# Balloon.net
KiCad netlist of a schematic drawn in EAGLE
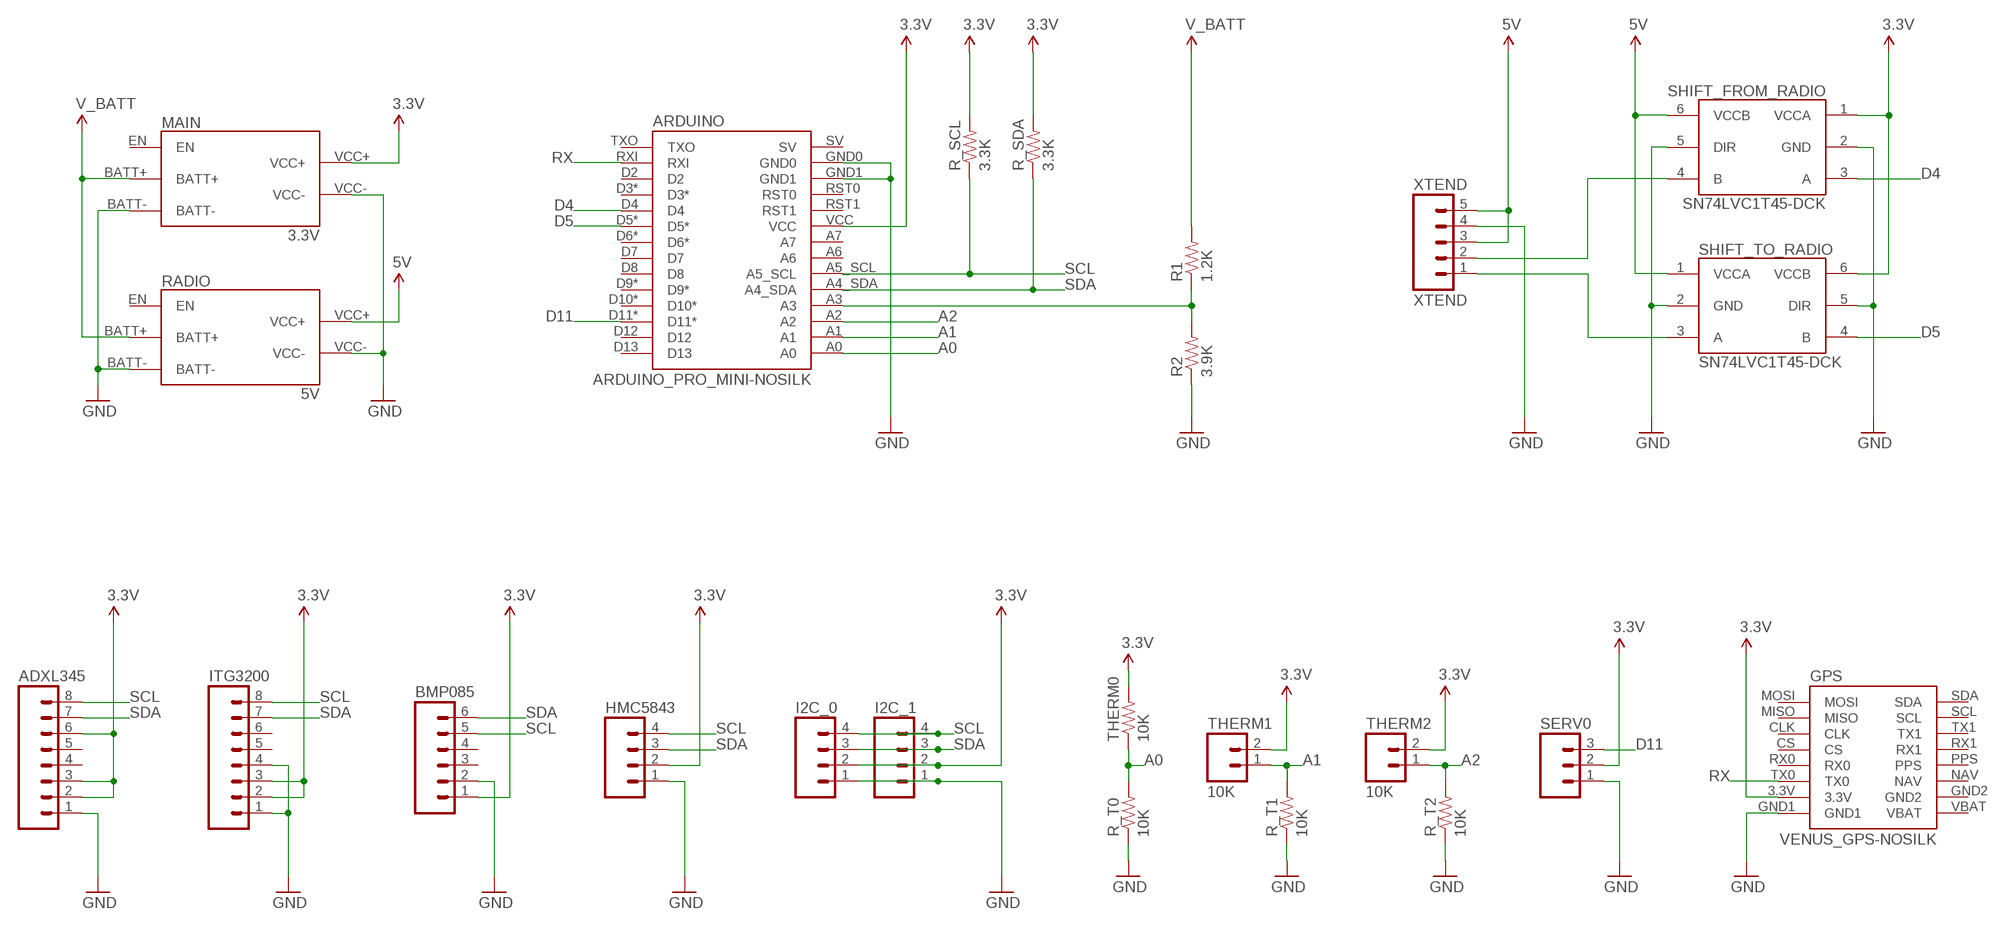
[diagram p0: schematic, sheet 1]

(export (version "E")
  (design (tool "Eeschema 10.0.6"))
  (components
    (comp (ref "ADXL345")
      (value "M081X08")
      (footprint "eagle-import:1X08")
      (libsource (lib "eagle-import") (part "M081X08"))
    )
    (comp (ref "ARDUINO")
      (value "ARDUINO_PRO_MINI-NOSILK")
      (footprint "eagle-import:ARDUINO_PRO_MINI-NOSILK")
      (libsource (lib "eagle-import") (part "ARDUINO_PRO_MINI-NOSILK"))
    )
    (comp (ref "BMP085")
      (value "M06SIP")
      (footprint "eagle-import:1X06")
      (libsource (lib "eagle-import") (part "M06SIP"))
    )
    (comp (ref "GPS")
      (value "VENUS_GPS-NOSILK")
      (footprint "eagle-import:VENUS_GPS-NOSILK")
      (libsource (lib "eagle-import") (part "VENUS_GPS-NOSILK"))
    )
    (comp (ref "HMC5843")
      (value "M04PTH")
      (footprint "eagle-import:1X04")
      (libsource (lib "eagle-import") (part "M04PTH"))
    )
    (comp (ref "I2C_0")
      (value "M04PTH")
      (footprint "eagle-import:1X04")
      (libsource (lib "eagle-import") (part "SparkFun-Connectors_M04PTH"))
    )
    (comp (ref "I2C_1")
      (value "M04PTH")
      (footprint "eagle-import:1X04")
      (libsource (lib "eagle-import") (part "SparkFun-Connectors_M04PTH"))
    )
    (comp (ref "ITG3200")
      (value "M081X08")
      (footprint "eagle-import:1X08")
      (libsource (lib "eagle-import") (part "M081X08"))
    )
    (comp (ref "MAIN")
      (value "3.3V")
      (footprint "eagle-import:POWER-TPS6300X-NOSILK")
      (libsource (lib "eagle-import") (part "POWER-TPS6300X-NOSILK"))
    )
    (comp (ref "R1")
      (value "1.2K")
      (footprint "eagle-import:0805")
      (libsource (lib "eagle-import") (part "RESISTOR0805-RES"))
    )
    (comp (ref "R2")
      (value "3.9K")
      (footprint "eagle-import:0805")
      (libsource (lib "eagle-import") (part "RESISTOR0805-RES"))
    )
    (comp (ref "RADIO")
      (value "5V")
      (footprint "eagle-import:POWER-TPS6300X-NOSILK")
      (libsource (lib "eagle-import") (part "POWER-TPS6300X-NOSILK"))
    )
    (comp (ref "R_SCL")
      (value "3.3K")
      (footprint "eagle-import:0805")
      (libsource (lib "eagle-import") (part "RESISTOR0805-RES"))
    )
    (comp (ref "R_SDA")
      (value "3.3K")
      (footprint "eagle-import:0805")
      (libsource (lib "eagle-import") (part "RESISTOR0805-RES"))
    )
    (comp (ref "R_T0")
      (value "10K")
      (footprint "eagle-import:0805")
      (libsource (lib "eagle-import") (part "RESISTOR0805-RES"))
    )
    (comp (ref "R_T1")
      (value "10K")
      (footprint "eagle-import:0805")
      (libsource (lib "eagle-import") (part "RESISTOR0805-RES"))
    )
    (comp (ref "R_T2")
      (value "10K")
      (footprint "eagle-import:0805")
      (libsource (lib "eagle-import") (part "RESISTOR0805-RES"))
    )
    (comp (ref "SERV0")
      (value "M03PTH")
      (footprint "eagle-import:1X03")
      (libsource (lib "eagle-import") (part "M03PTH"))
    )
    (comp (ref "SHIFT_FROM_RADIO")
      (value "SN74LVC1T45-DCK")
      (footprint "eagle-import:SC70")
      (libsource (lib "eagle-import") (part "SN74LVC1T45-DCK"))
    )
    (comp (ref "SHIFT_TO_RADIO")
      (value "SN74LVC1T45-DCK")
      (footprint "eagle-import:SC70")
      (libsource (lib "eagle-import") (part "SN74LVC1T45-DCK"))
    )
    (comp (ref "THERM0")
      (value "10K")
      (footprint "eagle-import:0805")
      (libsource (lib "eagle-import") (part "RESISTOR0805-RES"))
    )
    (comp (ref "THERM1")
      (value "10K")
      (footprint "eagle-import:JST-2-PTH")
      (libsource (lib "eagle-import") (part "M02JST-PTH-2"))
    )
    (comp (ref "THERM2")
      (value "10K")
      (footprint "eagle-import:JST-2-PTH")
      (libsource (lib "eagle-import") (part "M02JST-PTH-2"))
    )
    (comp (ref "XTEND")
      (value "XTEND")
      (footprint "eagle-import:JST-5-PTH-VERT")
      (libsource (lib "eagle-import") (part "M05JST-PTH-VERT"))
    )
  )
  (nets
    (net (code "1") (name "/A0") (class "Default")
      (node (ref "ARDUINO") (pin "A0") (pinfunction "A0_A0") (pintype "bidirectional"))
      (node (ref "R_T0") (pin "2") (pinfunction "2_2") (pintype "passive"))
      (node (ref "THERM0") (pin "1") (pinfunction "1_1") (pintype "passive"))
    )
    (net (code "2") (name "/A1") (class "Default")
      (node (ref "ARDUINO") (pin "A1") (pinfunction "A1_A1") (pintype "bidirectional"))
      (node (ref "R_T1") (pin "2") (pinfunction "2_2") (pintype "passive"))
      (node (ref "THERM1") (pin "1") (pinfunction "1_1") (pintype "passive"))
    )
    (net (code "3") (name "/A2") (class "Default")
      (node (ref "ARDUINO") (pin "A2") (pinfunction "A2_A2") (pintype "bidirectional"))
      (node (ref "R_T2") (pin "2") (pinfunction "2_2") (pintype "passive"))
      (node (ref "THERM2") (pin "1") (pinfunction "1_1") (pintype "passive"))
    )
    (net (code "4") (name "/D4") (class "Default")
      (node (ref "ARDUINO") (pin "D4") (pinfunction "D4_D4") (pintype "bidirectional"))
      (node (ref "SHIFT_FROM_RADIO") (pin "3") (pinfunction "A_3") (pintype "bidirectional"))
    )
    (net (code "5") (name "/D5") (class "Default")
      (node (ref "ARDUINO") (pin "D5*") (pinfunction "D5*_D5*") (pintype "bidirectional"))
      (node (ref "SHIFT_TO_RADIO") (pin "4") (pinfunction "B_4") (pintype "bidirectional"))
    )
    (net (code "6") (name "/D11") (class "Default")
      (node (ref "ARDUINO") (pin "D11*") (pinfunction "D11*_D11*") (pintype "bidirectional"))
      (node (ref "SERV0") (pin "3") (pinfunction "3_3") (pintype "passive"))
    )
    (net (code "7") (name "/RX") (class "Default")
      (node (ref "ARDUINO") (pin "RXI") (pinfunction "RXI_RXI") (pintype "bidirectional"))
      (node (ref "GPS") (pin "TX0") (pinfunction "TX0_TX0") (pintype "bidirectional"))
    )
    (net (code "8") (name "/SCL") (class "Default")
      (node (ref "ADXL345") (pin "8") (pinfunction "8_8") (pintype "passive"))
      (node (ref "ARDUINO") (pin "A5_SCL") (pinfunction "A5_SCL_A5_SCL") (pintype "bidirectional"))
      (node (ref "BMP085") (pin "5") (pinfunction "5_5") (pintype "passive"))
      (node (ref "HMC5843") (pin "4") (pinfunction "4_4") (pintype "passive"))
      (node (ref "I2C_0") (pin "4") (pinfunction "4_4") (pintype "passive"))
      (node (ref "I2C_1") (pin "4") (pinfunction "4_4") (pintype "passive"))
      (node (ref "ITG3200") (pin "8") (pinfunction "8_8") (pintype "passive"))
      (node (ref "R_SCL") (pin "1") (pinfunction "1_1") (pintype "passive"))
    )
    (net (code "9") (name "/SDA") (class "Default")
      (node (ref "ADXL345") (pin "7") (pinfunction "7_7") (pintype "passive"))
      (node (ref "ARDUINO") (pin "A4_SDA") (pinfunction "A4_SDA_A4_SDA") (pintype "bidirectional"))
      (node (ref "BMP085") (pin "6") (pinfunction "6_6") (pintype "passive"))
      (node (ref "HMC5843") (pin "3") (pinfunction "3_3") (pintype "passive"))
      (node (ref "I2C_0") (pin "3") (pinfunction "3_3") (pintype "passive"))
      (node (ref "I2C_1") (pin "3") (pinfunction "3_3") (pintype "passive"))
      (node (ref "ITG3200") (pin "7") (pinfunction "7_7") (pintype "passive"))
      (node (ref "R_SDA") (pin "1") (pinfunction "1_1") (pintype "passive"))
    )
    (net (code "10") (name "3.3V") (class "Default")
      (node (ref "ADXL345") (pin "2") (pinfunction "2_2") (pintype "passive"))
      (node (ref "ADXL345") (pin "3") (pinfunction "3_3") (pintype "passive"))
      (node (ref "ADXL345") (pin "6") (pinfunction "6_6") (pintype "passive"))
      (node (ref "ARDUINO") (pin "VCC") (pinfunction "VCC_VCC") (pintype "bidirectional"))
      (node (ref "BMP085") (pin "1") (pinfunction "1_1") (pintype "passive"))
      (node (ref "GPS") (pin "3.3V") (pinfunction "3.3V_3.3V") (pintype "bidirectional"))
      (node (ref "HMC5843") (pin "2") (pinfunction "2_2") (pintype "passive"))
      (node (ref "I2C_0") (pin "2") (pinfunction "2_2") (pintype "passive"))
      (node (ref "I2C_1") (pin "2") (pinfunction "2_2") (pintype "passive"))
      (node (ref "ITG3200") (pin "2") (pinfunction "2_2") (pintype "passive"))
      (node (ref "ITG3200") (pin "3") (pinfunction "3_3") (pintype "passive"))
      (node (ref "MAIN") (pin "VCC+") (pinfunction "VCC+_VCC+") (pintype "bidirectional"))
      (node (ref "R_SCL") (pin "2") (pinfunction "2_2") (pintype "passive"))
      (node (ref "R_SDA") (pin "2") (pinfunction "2_2") (pintype "passive"))
      (node (ref "SERV0") (pin "2") (pinfunction "2_2") (pintype "passive"))
      (node (ref "SHIFT_FROM_RADIO") (pin "1") (pinfunction "VCCA_1") (pintype "bidirectional"))
      (node (ref "SHIFT_TO_RADIO") (pin "6") (pinfunction "VCCB_6") (pintype "bidirectional"))
      (node (ref "THERM0") (pin "2") (pinfunction "2_2") (pintype "passive"))
      (node (ref "THERM1") (pin "2") (pinfunction "2_2") (pintype "passive"))
      (node (ref "THERM2") (pin "2") (pinfunction "2_2") (pintype "passive"))
    )
    (net (code "11") (name "5V") (class "Default")
      (node (ref "RADIO") (pin "VCC+") (pinfunction "VCC+_VCC+") (pintype "bidirectional"))
      (node (ref "SHIFT_FROM_RADIO") (pin "6") (pinfunction "VCCB_6") (pintype "bidirectional"))
      (node (ref "SHIFT_TO_RADIO") (pin "1") (pinfunction "VCCA_1") (pintype "bidirectional"))
      (node (ref "XTEND") (pin "3") (pinfunction "3_3") (pintype "passive"))
      (node (ref "XTEND") (pin "5") (pinfunction "5_5") (pintype "passive"))
    )
    (net (code "12") (name "GND") (class "Default")
      (node (ref "ADXL345") (pin "1") (pinfunction "1_1") (pintype "passive"))
      (node (ref "ARDUINO") (pin "GND0") (pinfunction "GND0_GND0") (pintype "bidirectional"))
      (node (ref "ARDUINO") (pin "GND1") (pinfunction "GND1_GND1") (pintype "bidirectional"))
      (node (ref "BMP085") (pin "2") (pinfunction "2_2") (pintype "passive"))
      (node (ref "GPS") (pin "GND1") (pinfunction "GND1_GND1") (pintype "bidirectional"))
      (node (ref "HMC5843") (pin "1") (pinfunction "1_1") (pintype "passive"))
      (node (ref "I2C_0") (pin "1") (pinfunction "1_1") (pintype "passive"))
      (node (ref "I2C_1") (pin "1") (pinfunction "1_1") (pintype "passive"))
      (node (ref "ITG3200") (pin "1") (pinfunction "1_1") (pintype "passive"))
      (node (ref "ITG3200") (pin "4") (pinfunction "4_4") (pintype "passive"))
      (node (ref "MAIN") (pin "BATT-") (pinfunction "BATT-_BATT-") (pintype "bidirectional"))
      (node (ref "MAIN") (pin "VCC-") (pinfunction "VCC-_VCC-") (pintype "bidirectional"))
      (node (ref "R2") (pin "1") (pinfunction "1_1") (pintype "passive"))
      (node (ref "RADIO") (pin "BATT-") (pinfunction "BATT-_BATT-") (pintype "bidirectional"))
      (node (ref "RADIO") (pin "VCC-") (pinfunction "VCC-_VCC-") (pintype "bidirectional"))
      (node (ref "R_T0") (pin "1") (pinfunction "1_1") (pintype "passive"))
      (node (ref "R_T1") (pin "1") (pinfunction "1_1") (pintype "passive"))
      (node (ref "R_T2") (pin "1") (pinfunction "1_1") (pintype "passive"))
      (node (ref "SERV0") (pin "1") (pinfunction "1_1") (pintype "passive"))
      (node (ref "SHIFT_FROM_RADIO") (pin "2") (pinfunction "GND_2") (pintype "bidirectional"))
      (node (ref "SHIFT_FROM_RADIO") (pin "5") (pinfunction "DIR_5") (pintype "bidirectional"))
      (node (ref "SHIFT_TO_RADIO") (pin "2") (pinfunction "GND_2") (pintype "bidirectional"))
      (node (ref "SHIFT_TO_RADIO") (pin "5") (pinfunction "DIR_5") (pintype "bidirectional"))
      (node (ref "XTEND") (pin "4") (pinfunction "4_4") (pintype "passive"))
    )
    (net (code "13") (name "Net-(ARDUINO-PadA3)") (class "Default")
      (node (ref "ARDUINO") (pin "A3") (pinfunction "A3_A3") (pintype "bidirectional"))
      (node (ref "R1") (pin "1") (pinfunction "1_1") (pintype "passive"))
      (node (ref "R2") (pin "2") (pinfunction "2_2") (pintype "passive"))
    )
    (net (code "14") (name "Net-(SHIFT_FROM_RADIO-B)") (class "Default")
      (node (ref "SHIFT_FROM_RADIO") (pin "4") (pinfunction "B_4") (pintype "bidirectional"))
      (node (ref "XTEND") (pin "2") (pinfunction "2_2") (pintype "passive"))
    )
    (net (code "15") (name "Net-(SHIFT_TO_RADIO-A)") (class "Default")
      (node (ref "SHIFT_TO_RADIO") (pin "3") (pinfunction "A_3") (pintype "bidirectional"))
      (node (ref "XTEND") (pin "1") (pinfunction "1_1") (pintype "passive"))
    )
    (net (code "16") (name "V_BATT") (class "Default")
      (node (ref "MAIN") (pin "BATT+") (pinfunction "BATT+_BATT+") (pintype "bidirectional"))
      (node (ref "R1") (pin "2") (pinfunction "2_2") (pintype "passive"))
      (node (ref "RADIO") (pin "BATT+") (pinfunction "BATT+_BATT+") (pintype "bidirectional"))
    )
    (net (code "17") (name "unconnected-(ADXL345-Pad4)") (class "Default")
      (node (ref "ADXL345") (pin "4") (pinfunction "4_4") (pintype "passive"))
    )
    (net (code "18") (name "unconnected-(ADXL345-Pad5)") (class "Default")
      (node (ref "ADXL345") (pin "5") (pinfunction "5_5") (pintype "passive"))
    )
    (net (code "19") (name "unconnected-(ARDUINO-PadA6)") (class "Default")
      (node (ref "ARDUINO") (pin "A6") (pinfunction "A6_A6") (pintype "bidirectional"))
    )
    (net (code "20") (name "unconnected-(ARDUINO-PadA7)") (class "Default")
      (node (ref "ARDUINO") (pin "A7") (pinfunction "A7_A7") (pintype "bidirectional"))
    )
    (net (code "21") (name "unconnected-(ARDUINO-PadD2)") (class "Default")
      (node (ref "ARDUINO") (pin "D2") (pinfunction "D2_D2") (pintype "bidirectional"))
    )
    (net (code "22") (name "unconnected-(ARDUINO-PadD3*)") (class "Default")
      (node (ref "ARDUINO") (pin "D3*") (pinfunction "D3*_D3*") (pintype "bidirectional"))
    )
    (net (code "23") (name "unconnected-(ARDUINO-PadD6*)") (class "Default")
      (node (ref "ARDUINO") (pin "D6*") (pinfunction "D6*_D6*") (pintype "bidirectional"))
    )
    (net (code "24") (name "unconnected-(ARDUINO-PadD7)") (class "Default")
      (node (ref "ARDUINO") (pin "D7") (pinfunction "D7_D7") (pintype "bidirectional"))
    )
    (net (code "25") (name "unconnected-(ARDUINO-PadD8)") (class "Default")
      (node (ref "ARDUINO") (pin "D8") (pinfunction "D8_D8") (pintype "bidirectional"))
    )
    (net (code "26") (name "unconnected-(ARDUINO-PadD9*)") (class "Default")
      (node (ref "ARDUINO") (pin "D9*") (pinfunction "D9*_D9*") (pintype "bidirectional"))
    )
    (net (code "27") (name "unconnected-(ARDUINO-PadD10*)") (class "Default")
      (node (ref "ARDUINO") (pin "D10*") (pinfunction "D10*_D10*") (pintype "bidirectional"))
    )
    (net (code "28") (name "unconnected-(ARDUINO-PadD12)") (class "Default")
      (node (ref "ARDUINO") (pin "D12") (pinfunction "D12_D12") (pintype "bidirectional"))
    )
    (net (code "29") (name "unconnected-(ARDUINO-PadD13)") (class "Default")
      (node (ref "ARDUINO") (pin "D13") (pinfunction "D13_D13") (pintype "bidirectional"))
    )
    (net (code "30") (name "unconnected-(ARDUINO-PadRST0)") (class "Default")
      (node (ref "ARDUINO") (pin "RST0") (pinfunction "RST0_RST0") (pintype "bidirectional"))
    )
    (net (code "31") (name "unconnected-(ARDUINO-PadRST1)") (class "Default")
      (node (ref "ARDUINO") (pin "RST1") (pinfunction "RST1_RST1") (pintype "bidirectional"))
    )
    (net (code "32") (name "unconnected-(ARDUINO-PadSV)") (class "Default")
      (node (ref "ARDUINO") (pin "SV") (pinfunction "SV_SV") (pintype "bidirectional"))
    )
    (net (code "33") (name "unconnected-(ARDUINO-PadTXO)") (class "Default")
      (node (ref "ARDUINO") (pin "TXO") (pinfunction "TXO_TXO") (pintype "bidirectional"))
    )
    (net (code "34") (name "unconnected-(BMP085-Pad3)") (class "Default")
      (node (ref "BMP085") (pin "3") (pinfunction "3_3") (pintype "passive"))
    )
    (net (code "35") (name "unconnected-(BMP085-Pad4)") (class "Default")
      (node (ref "BMP085") (pin "4") (pinfunction "4_4") (pintype "passive"))
    )
    (net (code "36") (name "unconnected-(GPS-PadCLK)") (class "Default")
      (node (ref "GPS") (pin "CLK") (pinfunction "CLK_CLK") (pintype "bidirectional"))
    )
    (net (code "37") (name "unconnected-(GPS-PadCS)") (class "Default")
      (node (ref "GPS") (pin "CS") (pinfunction "CS_CS") (pintype "bidirectional"))
    )
    (net (code "38") (name "unconnected-(GPS-PadGND2)") (class "Default")
      (node (ref "GPS") (pin "GND2") (pinfunction "GND2_GND2") (pintype "bidirectional"))
    )
    (net (code "39") (name "unconnected-(GPS-PadMISO)") (class "Default")
      (node (ref "GPS") (pin "MISO") (pinfunction "MISO_MISO") (pintype "bidirectional"))
    )
    (net (code "40") (name "unconnected-(GPS-PadMOSI)") (class "Default")
      (node (ref "GPS") (pin "MOSI") (pinfunction "MOSI_MOSI") (pintype "bidirectional"))
    )
    (net (code "41") (name "unconnected-(GPS-PadNAV)") (class "Default")
      (node (ref "GPS") (pin "NAV") (pinfunction "NAV_NAV") (pintype "bidirectional"))
    )
    (net (code "42") (name "unconnected-(GPS-PadPPS)") (class "Default")
      (node (ref "GPS") (pin "PPS") (pinfunction "PPS_PPS") (pintype "bidirectional"))
    )
    (net (code "43") (name "unconnected-(GPS-PadRX0)") (class "Default")
      (node (ref "GPS") (pin "RX0") (pinfunction "RX0_RX0") (pintype "bidirectional"))
    )
    (net (code "44") (name "unconnected-(GPS-PadRX1)") (class "Default")
      (node (ref "GPS") (pin "RX1") (pinfunction "RX1_RX1") (pintype "bidirectional"))
    )
    (net (code "45") (name "unconnected-(GPS-PadSCL)") (class "Default")
      (node (ref "GPS") (pin "SCL") (pinfunction "SCL_SCL") (pintype "bidirectional"))
    )
    (net (code "46") (name "unconnected-(GPS-PadSDA)") (class "Default")
      (node (ref "GPS") (pin "SDA") (pinfunction "SDA_SDA") (pintype "bidirectional"))
    )
    (net (code "47") (name "unconnected-(GPS-PadTX1)") (class "Default")
      (node (ref "GPS") (pin "TX1") (pinfunction "TX1_TX1") (pintype "bidirectional"))
    )
    (net (code "48") (name "unconnected-(GPS-PadVBAT)") (class "Default")
      (node (ref "GPS") (pin "VBAT") (pinfunction "VBAT_VBAT") (pintype "bidirectional"))
    )
    (net (code "49") (name "unconnected-(ITG3200-Pad5)") (class "Default")
      (node (ref "ITG3200") (pin "5") (pinfunction "5_5") (pintype "passive"))
    )
    (net (code "50") (name "unconnected-(ITG3200-Pad6)") (class "Default")
      (node (ref "ITG3200") (pin "6") (pinfunction "6_6") (pintype "passive"))
    )
    (net (code "51") (name "unconnected-(MAIN-PadEN)") (class "Default")
      (node (ref "MAIN") (pin "EN") (pinfunction "EN_EN") (pintype "bidirectional"))
    )
    (net (code "52") (name "unconnected-(RADIO-PadEN)") (class "Default")
      (node (ref "RADIO") (pin "EN") (pinfunction "EN_EN") (pintype "bidirectional"))
    )
  )
)
